# 08_HDMI.net
KiCad netlist of a schematic drawn in Altium Designer
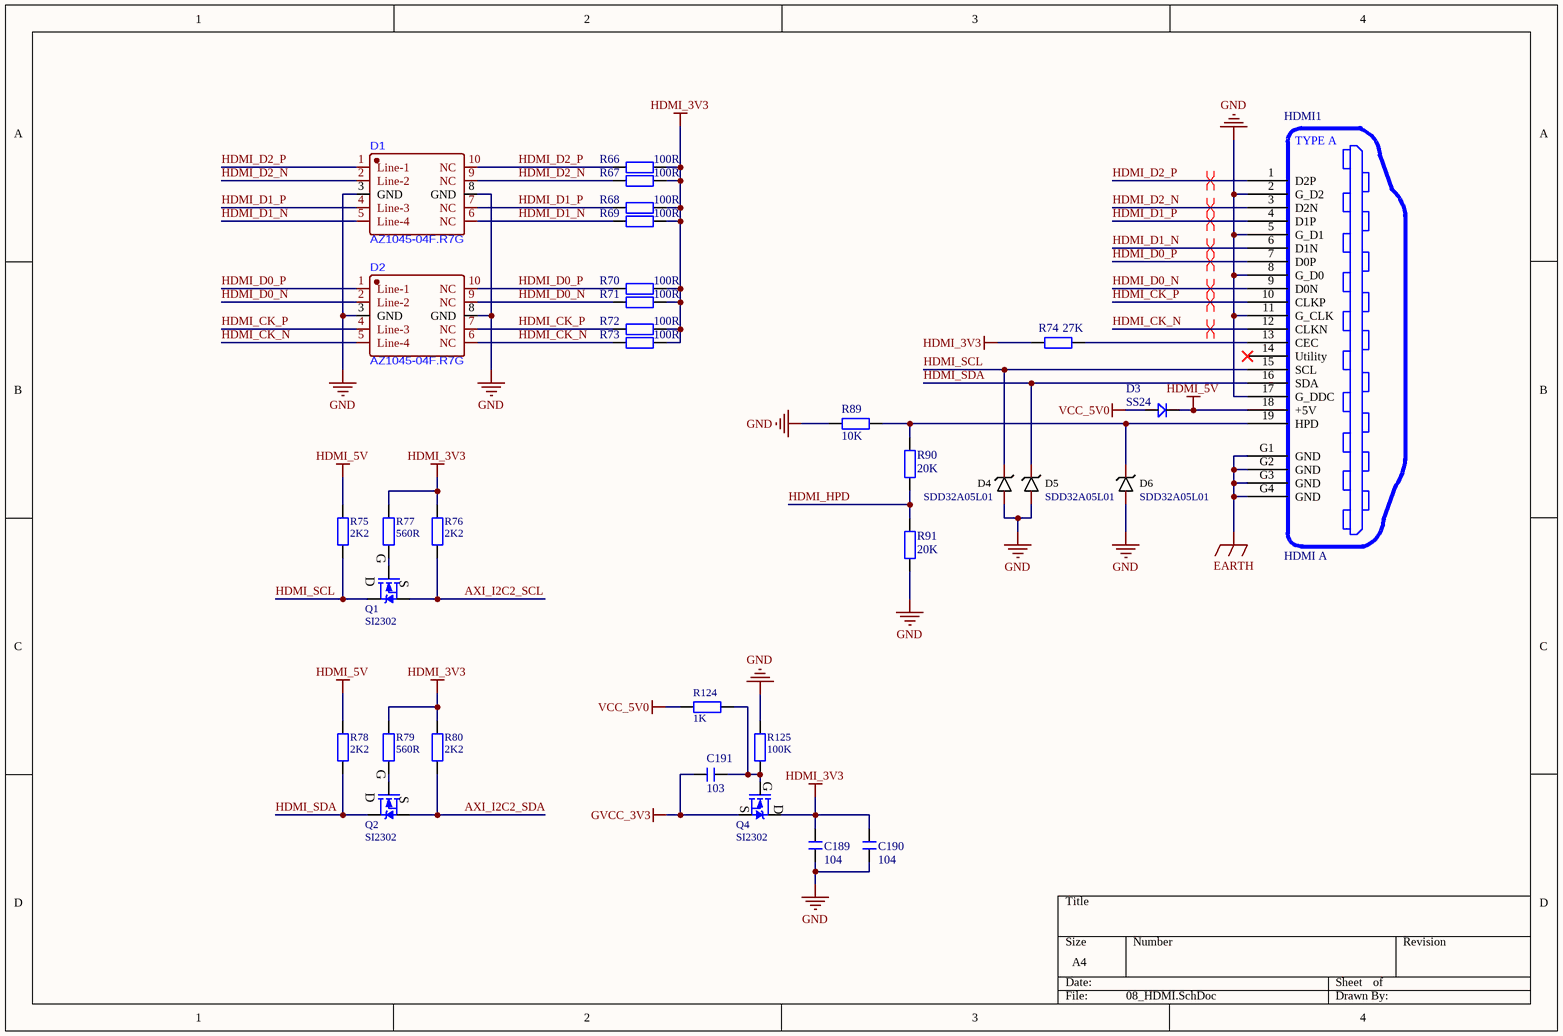
[diagram p0: 08_HDMI.SchDoc]

(export (version "E")
  (design (tool "Eeschema 10.0.6"))
  (components
    (comp (ref "C189")
      (value "104")
      (footprint "C 0603")
      (description "无极性贴片电容")
      (fields (field (name "版权归属") "源创客"))
      (libsource (lib "STM32MP15x底板封装库V1.4") (part "C"))
    )
    (comp (ref "C190")
      (value "104")
      (footprint "C 0603")
      (description "无极性贴片电容")
      (fields (field (name "版权归属") "源创客"))
      (libsource (lib "STM32MP15x底板封装库V1.4") (part "C"))
    )
    (comp (ref "C191")
      (value "103")
      (footprint "C 0603")
      (description "无极性贴片电容")
      (fields (field (name "版权归属") "源创客"))
      (libsource (lib "STM32MP15x底板封装库V1.4") (part "C"))
    )
    (comp (ref "D1")
      (value "AZ1045-04F.R7G")
      (footprint "AZ1045-04F")
      (libsource (lib "AZ1045-04F") (part "AZ1045-04F.R7G"))
    )
    (comp (ref "D2")
      (value "AZ1045-04F.R7G")
      (footprint "AZ1045-04F")
      (libsource (lib "AZ1045-04F") (part "AZ1045-04F.R7G"))
    )
    (comp (ref "D3")
      (value "SS24")
      (footprint "SMA")
      (description "肖特基二极管")
      (fields (field (name "版权归属") "源创客"))
      (libsource (lib "STM32MP15x底板封装库V1.4") (part "SS14"))
    )
    (comp (ref "D4")
      (value "SDD32A05L01")
      (footprint "SOD-323")
      (fields (field (name "MANUFACTURER") "Brightking(君耀电子)"))
      (libsource (lib "SDD32A05L01") (part "SDD32A05L01"))
    )
    (comp (ref "D5")
      (value "SDD32A05L01")
      (footprint "SOD-323")
      (fields (field (name "MANUFACTURER") "Brightking(君耀电子)"))
      (libsource (lib "SDD32A05L01") (part "SDD32A05L01"))
    )
    (comp (ref "D6")
      (value "SDD32A05L01")
      (footprint "SOD-323")
      (fields (field (name "MANUFACTURER") "Brightking(君耀电子)"))
      (libsource (lib "SDD32A05L01") (part "SDD32A05L01"))
    )
    (comp (ref "HDMI1")
      (value "HDMI A")
      (footprint "HDMI-A")
      (description "HDMI座子")
      (libsource (lib "STM32MP15x底板封装库V1.4") (part "HDMI-A-19P"))
    )
    (comp (ref "Q1")
      (value "SI2302")
      (footprint "SOT23-3L")
      (description "N沟道场效应管")
      (fields (field (name "版权归属") "源创客"))
      (libsource (lib "STM32MP157核心板封装库V1.2") (part "SI2302"))
    )
    (comp (ref "Q2")
      (value "SI2302")
      (footprint "SOT23-3L")
      (description "N沟道场效应管")
      (fields (field (name "版权归属") "源创客"))
      (libsource (lib "STM32MP157核心板封装库V1.2") (part "SI2302"))
    )
    (comp (ref "Q4")
      (value "SI2302")
      (footprint "SOT23-3L")
      (description "N沟道场效应管")
      (fields (field (name "版权归属") "源创客"))
      (libsource (lib "STM32MP157核心板封装库V1.2") (part "SI2302"))
    )
    (comp (ref "R66")
      (value "100R")
      (footprint "R 0402")
      (description "贴片电阻")
      (fields (field (name "版权归属") "源创客"))
      (libsource (lib "STM32MP15x底板封装库V1.4") (part "R"))
    )
    (comp (ref "R67")
      (value "100R")
      (footprint "R 0402")
      (description "贴片电阻")
      (fields (field (name "版权归属") "源创客"))
      (libsource (lib "STM32MP15x底板封装库V1.4") (part "R"))
    )
    (comp (ref "R68")
      (value "100R")
      (footprint "R 0402")
      (description "贴片电阻")
      (fields (field (name "版权归属") "源创客"))
      (libsource (lib "STM32MP15x底板封装库V1.4") (part "R"))
    )
    (comp (ref "R69")
      (value "100R")
      (footprint "R 0402")
      (description "贴片电阻")
      (fields (field (name "版权归属") "源创客"))
      (libsource (lib "STM32MP15x底板封装库V1.4") (part "R"))
    )
    (comp (ref "R70")
      (value "100R")
      (footprint "R 0402")
      (description "贴片电阻")
      (fields (field (name "版权归属") "源创客"))
      (libsource (lib "STM32MP15x底板封装库V1.4") (part "R"))
    )
    (comp (ref "R71")
      (value "100R")
      (footprint "R 0402")
      (description "贴片电阻")
      (fields (field (name "版权归属") "源创客"))
      (libsource (lib "STM32MP15x底板封装库V1.4") (part "R"))
    )
    (comp (ref "R72")
      (value "100R")
      (footprint "R 0402")
      (description "贴片电阻")
      (fields (field (name "版权归属") "源创客"))
      (libsource (lib "STM32MP15x底板封装库V1.4") (part "R"))
    )
    (comp (ref "R73")
      (value "100R")
      (footprint "R 0402")
      (description "贴片电阻")
      (fields (field (name "版权归属") "源创客"))
      (libsource (lib "STM32MP15x底板封装库V1.4") (part "R"))
    )
    (comp (ref "R74")
      (value "27K")
      (footprint "R 0402")
      (description "贴片电阻")
      (fields (field (name "版权归属") "源创客"))
      (libsource (lib "STM32MP15x底板封装库V1.4") (part "R"))
    )
    (comp (ref "R75")
      (value "2K2")
      (footprint "R 0603")
      (description "贴片电阻")
      (fields (field (name "版权归属") "源创客"))
      (libsource (lib "STM32MP157核心板封装库V1.2") (part "R"))
    )
    (comp (ref "R76")
      (value "2K2")
      (footprint "R 0603")
      (description "贴片电阻")
      (fields (field (name "版权归属") "源创客"))
      (libsource (lib "STM32MP157核心板封装库V1.2") (part "R"))
    )
    (comp (ref "R77")
      (value "560R")
      (footprint "R 0603")
      (description "贴片电阻")
      (fields (field (name "版权归属") "源创客"))
      (libsource (lib "STM32MP157核心板封装库V1.2") (part "R"))
    )
    (comp (ref "R78")
      (value "2K2")
      (footprint "R 0603")
      (description "贴片电阻")
      (fields (field (name "版权归属") "源创客"))
      (libsource (lib "STM32MP157核心板封装库V1.2") (part "R"))
    )
    (comp (ref "R79")
      (value "560R")
      (footprint "R 0603")
      (description "贴片电阻")
      (fields (field (name "版权归属") "源创客"))
      (libsource (lib "STM32MP157核心板封装库V1.2") (part "R"))
    )
    (comp (ref "R80")
      (value "2K2")
      (footprint "R 0603")
      (description "贴片电阻")
      (fields (field (name "版权归属") "源创客"))
      (libsource (lib "STM32MP157核心板封装库V1.2") (part "R"))
    )
    (comp (ref "R89")
      (value "10K")
      (footprint "R 0603")
      (description "贴片电阻")
      (fields (field (name "版权归属") "源创客"))
      (libsource (lib "STM32MP15x底板封装库V1.4") (part "R"))
    )
    (comp (ref "R90")
      (value "20K")
      (footprint "R 0603")
      (description "贴片电阻")
      (fields (field (name "版权归属") "源创客"))
      (libsource (lib "STM32MP15x底板封装库V1.4") (part "R"))
    )
    (comp (ref "R91")
      (value "20K")
      (footprint "R 0603")
      (description "贴片电阻")
      (fields (field (name "版权归属") "源创客"))
      (libsource (lib "STM32MP15x底板封装库V1.4") (part "R"))
    )
    (comp (ref "R124")
      (value "1K")
      (footprint "R 0603")
      (description "贴片电阻")
      (fields (field (name "版权归属") "源创客"))
      (libsource (lib "STM32MP157核心板封装库V1.2") (part "R"))
    )
    (comp (ref "R125")
      (value "100K")
      (footprint "R 0603")
      (description "贴片电阻")
      (fields (field (name "版权归属") "源创客"))
      (libsource (lib "STM32MP157核心板封装库V1.2") (part "R"))
    )
  )
  (nets
    (net (code "1") (name "/AXI_I2C2_SCL") (class "Default")
      (node (ref "Q1") (pin "2") (pinfunction "S_2") (pintype "passive"))
      (node (ref "R76") (pin "1") (pinfunction "1_1") (pintype "passive"))
    )
    (net (code "2") (name "/AXI_I2C2_SDA") (class "Default")
      (node (ref "Q2") (pin "2") (pinfunction "S_2") (pintype "passive"))
      (node (ref "R80") (pin "1") (pinfunction "1_1") (pintype "passive"))
    )
    (net (code "3") (name "/HDMI_CK_N") (class "Default")
      (node (ref "D2") (pin "5") (pinfunction "Line-4_5") (pintype "passive"))
      (node (ref "D2") (pin "6") (pinfunction "NC_6") (pintype "passive"))
      (node (ref "HDMI1") (pin "12") (pinfunction "CLKN_12") (pintype "passive"))
      (node (ref "R73") (pin "1") (pinfunction "1_1") (pintype "passive"))
    )
    (net (code "4") (name "/HDMI_CK_P") (class "Default")
      (node (ref "D2") (pin "4") (pinfunction "Line-3_4") (pintype "passive"))
      (node (ref "D2") (pin "7") (pinfunction "NC_7") (pintype "passive"))
      (node (ref "HDMI1") (pin "10") (pinfunction "CLKP_10") (pintype "passive"))
      (node (ref "R72") (pin "1") (pinfunction "1_1") (pintype "passive"))
    )
    (net (code "5") (name "/HDMI_D0_N") (class "Default")
      (node (ref "D2") (pin "2") (pinfunction "Line-2_2") (pintype "passive"))
      (node (ref "D2") (pin "9") (pinfunction "NC_9") (pintype "passive"))
      (node (ref "HDMI1") (pin "9") (pinfunction "D0N_9") (pintype "passive"))
      (node (ref "R71") (pin "1") (pinfunction "1_1") (pintype "passive"))
    )
    (net (code "6") (name "/HDMI_D0_P") (class "Default")
      (node (ref "D2") (pin "1") (pinfunction "Line-1_1") (pintype "passive"))
      (node (ref "D2") (pin "10") (pinfunction "NC_10") (pintype "passive"))
      (node (ref "HDMI1") (pin "7") (pinfunction "D0P_7") (pintype "passive"))
      (node (ref "R70") (pin "1") (pinfunction "1_1") (pintype "passive"))
    )
    (net (code "7") (name "/HDMI_D1_N") (class "Default")
      (node (ref "D1") (pin "5") (pinfunction "Line-4_5") (pintype "passive"))
      (node (ref "D1") (pin "6") (pinfunction "NC_6") (pintype "passive"))
      (node (ref "HDMI1") (pin "6") (pinfunction "D1N_6") (pintype "passive"))
      (node (ref "R69") (pin "1") (pinfunction "1_1") (pintype "passive"))
    )
    (net (code "8") (name "/HDMI_D1_P") (class "Default")
      (node (ref "D1") (pin "4") (pinfunction "Line-3_4") (pintype "passive"))
      (node (ref "D1") (pin "7") (pinfunction "NC_7") (pintype "passive"))
      (node (ref "HDMI1") (pin "4") (pinfunction "D1P_4") (pintype "passive"))
      (node (ref "R68") (pin "1") (pinfunction "1_1") (pintype "passive"))
    )
    (net (code "9") (name "/HDMI_D2_N") (class "Default")
      (node (ref "D1") (pin "2") (pinfunction "Line-2_2") (pintype "passive"))
      (node (ref "D1") (pin "9") (pinfunction "NC_9") (pintype "passive"))
      (node (ref "HDMI1") (pin "3") (pinfunction "D2N_3") (pintype "passive"))
      (node (ref "R67") (pin "1") (pinfunction "1_1") (pintype "passive"))
    )
    (net (code "10") (name "/HDMI_D2_P") (class "Default")
      (node (ref "D1") (pin "1") (pinfunction "Line-1_1") (pintype "passive"))
      (node (ref "D1") (pin "10") (pinfunction "NC_10") (pintype "passive"))
      (node (ref "HDMI1") (pin "1") (pinfunction "D2P_1") (pintype "passive"))
      (node (ref "R66") (pin "1") (pinfunction "1_1") (pintype "passive"))
    )
    (net (code "11") (name "/HDMI_HPD") (class "Default")
      (node (ref "R90") (pin "1") (pinfunction "1_1") (pintype "passive"))
      (node (ref "R91") (pin "2") (pinfunction "2_2") (pintype "passive"))
    )
    (net (code "12") (name "/HDMI_SCL") (class "Default")
      (node (ref "D4") (pin "1") (pinfunction "C_1") (pintype "passive"))
      (node (ref "HDMI1") (pin "15") (pinfunction "SCL_15") (pintype "passive"))
      (node (ref "Q1") (pin "3") (pinfunction "D_3") (pintype "passive"))
      (node (ref "R75") (pin "1") (pinfunction "1_1") (pintype "passive"))
    )
    (net (code "13") (name "/HDMI_SDA") (class "Default")
      (node (ref "D5") (pin "1") (pinfunction "C_1") (pintype "passive"))
      (node (ref "HDMI1") (pin "16") (pinfunction "SDA_16") (pintype "passive"))
      (node (ref "Q2") (pin "3") (pinfunction "D_3") (pintype "passive"))
      (node (ref "R78") (pin "1") (pinfunction "1_1") (pintype "passive"))
    )
    (net (code "14") (name "EARTH") (class "Default")
      (node (ref "HDMI1") (pin "G1") (pinfunction "GND_G1") (pintype "passive"))
      (node (ref "HDMI1") (pin "G2") (pinfunction "GND_G2") (pintype "passive"))
      (node (ref "HDMI1") (pin "G3") (pinfunction "GND_G3") (pintype "passive"))
      (node (ref "HDMI1") (pin "G4") (pinfunction "GND_G4") (pintype "passive"))
    )
    (net (code "15") (name "GND") (class "Default")
      (node (ref "C189") (pin "1") (pinfunction "1_1") (pintype "passive"))
      (node (ref "C190") (pin "1") (pinfunction "1_1") (pintype "passive"))
      (node (ref "D1") (pin "3") (pinfunction "GND_3") (pintype "passive"))
      (node (ref "D1") (pin "8") (pinfunction "GND_8") (pintype "passive"))
      (node (ref "D2") (pin "3") (pinfunction "GND_3") (pintype "passive"))
      (node (ref "D2") (pin "8") (pinfunction "GND_8") (pintype "passive"))
      (node (ref "D4") (pin "2") (pinfunction "A_2") (pintype "passive"))
      (node (ref "D5") (pin "2") (pinfunction "A_2") (pintype "passive"))
      (node (ref "D6") (pin "2") (pinfunction "A_2") (pintype "passive"))
      (node (ref "HDMI1") (pin "11") (pinfunction "G_CLK_11") (pintype "passive"))
      (node (ref "HDMI1") (pin "17") (pinfunction "G_DDC_17") (pintype "passive"))
      (node (ref "HDMI1") (pin "2") (pinfunction "G_D2_2") (pintype "passive"))
      (node (ref "HDMI1") (pin "5") (pinfunction "G_D1_5") (pintype "passive"))
      (node (ref "HDMI1") (pin "8") (pinfunction "G_D0_8") (pintype "passive"))
      (node (ref "R125") (pin "2") (pinfunction "2_2") (pintype "passive"))
      (node (ref "R89") (pin "1") (pinfunction "1_1") (pintype "passive"))
      (node (ref "R91") (pin "1") (pinfunction "1_1") (pintype "passive"))
    )
    (net (code "16") (name "GVCC_3V3") (class "Default")
      (node (ref "C191") (pin "1") (pinfunction "1_1") (pintype "passive"))
      (node (ref "Q4") (pin "2") (pinfunction "S_2") (pintype "passive"))
    )
    (net (code "17") (name "HDMI_3V3") (class "Default")
      (node (ref "C189") (pin "2") (pinfunction "2_2") (pintype "passive"))
      (node (ref "C190") (pin "2") (pinfunction "2_2") (pintype "passive"))
      (node (ref "Q4") (pin "3") (pinfunction "D_3") (pintype "passive"))
      (node (ref "R66") (pin "2") (pinfunction "2_2") (pintype "passive"))
      (node (ref "R67") (pin "2") (pinfunction "2_2") (pintype "passive"))
      (node (ref "R68") (pin "2") (pinfunction "2_2") (pintype "passive"))
      (node (ref "R69") (pin "2") (pinfunction "2_2") (pintype "passive"))
      (node (ref "R70") (pin "2") (pinfunction "2_2") (pintype "passive"))
      (node (ref "R71") (pin "2") (pinfunction "2_2") (pintype "passive"))
      (node (ref "R72") (pin "2") (pinfunction "2_2") (pintype "passive"))
      (node (ref "R73") (pin "2") (pinfunction "2_2") (pintype "passive"))
      (node (ref "R74") (pin "1") (pinfunction "1_1") (pintype "passive"))
      (node (ref "R76") (pin "2") (pinfunction "2_2") (pintype "passive"))
      (node (ref "R77") (pin "2") (pinfunction "2_2") (pintype "passive"))
      (node (ref "R79") (pin "2") (pinfunction "2_2") (pintype "passive"))
      (node (ref "R80") (pin "2") (pinfunction "2_2") (pintype "passive"))
    )
    (net (code "18") (name "HDMI_5V") (class "Default")
      (node (ref "D3") (pin "2") (pinfunction "K_2") (pintype "passive"))
      (node (ref "HDMI1") (pin "18") (pinfunction "+5V_18") (pintype "passive"))
      (node (ref "R75") (pin "2") (pinfunction "2_2") (pintype "passive"))
      (node (ref "R78") (pin "2") (pinfunction "2_2") (pintype "passive"))
    )
    (net (code "19") (name "Net-(D6-C)") (class "Default")
      (node (ref "D6") (pin "1") (pinfunction "C_1") (pintype "passive"))
      (node (ref "HDMI1") (pin "19") (pinfunction "HPD_19") (pintype "passive"))
      (node (ref "R89") (pin "2") (pinfunction "2_2") (pintype "passive"))
      (node (ref "R90") (pin "2") (pinfunction "2_2") (pintype "passive"))
    )
    (net (code "20") (name "Net-(HDMI1-CEC)") (class "Default")
      (node (ref "HDMI1") (pin "13") (pinfunction "CEC_13") (pintype "passive"))
      (node (ref "R74") (pin "2") (pinfunction "2_2") (pintype "passive"))
    )
    (net (code "21") (name "Net-(Q1-G)") (class "Default")
      (node (ref "Q1") (pin "1") (pinfunction "G_1") (pintype "passive"))
      (node (ref "R77") (pin "1") (pinfunction "1_1") (pintype "passive"))
    )
    (net (code "22") (name "Net-(Q2-G)") (class "Default")
      (node (ref "Q2") (pin "1") (pinfunction "G_1") (pintype "passive"))
      (node (ref "R79") (pin "1") (pinfunction "1_1") (pintype "passive"))
    )
    (net (code "23") (name "Net-(Q4-G)") (class "Default")
      (node (ref "C191") (pin "2") (pinfunction "2_2") (pintype "passive"))
      (node (ref "Q4") (pin "1") (pinfunction "G_1") (pintype "passive"))
      (node (ref "R124") (pin "1") (pinfunction "1_1") (pintype "passive"))
      (node (ref "R125") (pin "1") (pinfunction "1_1") (pintype "passive"))
    )
    (net (code "24") (name "VCC_5V0") (class "Default")
      (node (ref "D3") (pin "1") (pinfunction "A_1") (pintype "passive"))
      (node (ref "R124") (pin "2") (pinfunction "2_2") (pintype "passive"))
    )
    (net (code "25") (name "unconnected-(HDMI1-Utility-Pad14)") (class "Default")
      (node (ref "HDMI1") (pin "14") (pinfunction "Utility_14") (pintype "passive+no_connect"))
    )
  )
)
